# SymphonyLights_SOC_v1_1.net
KiCad netlist of a schematic drawn in Altium Designer
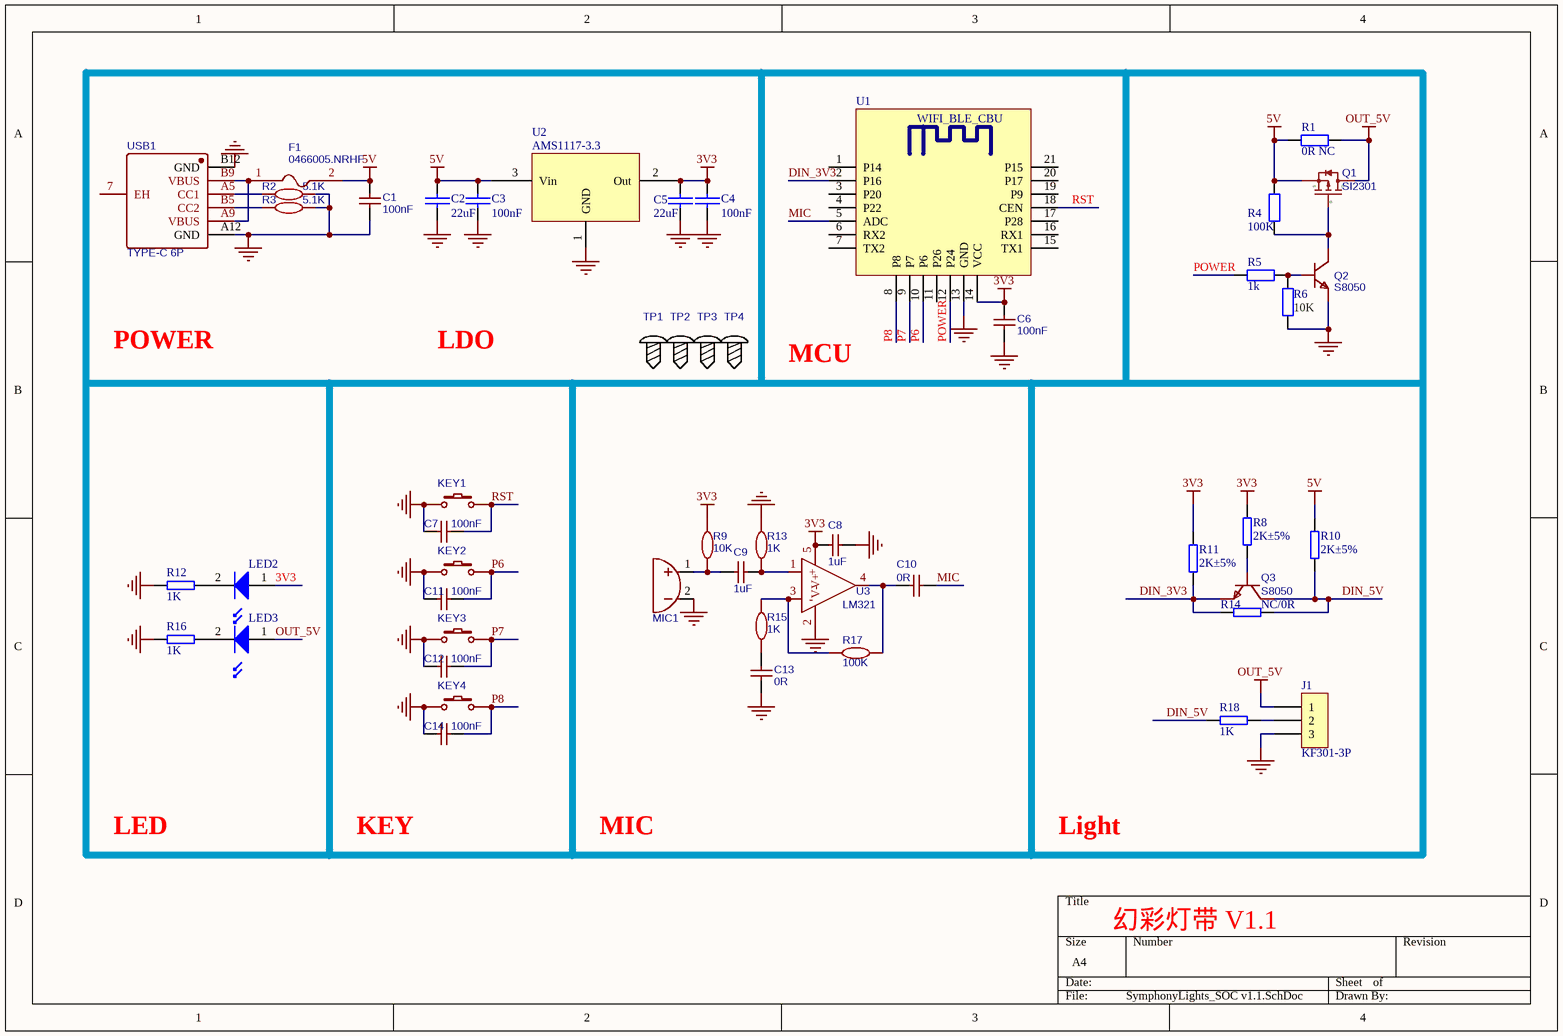
[diagram p0: SymphonyLights_SOC v1.1.SchDoc]

(export (version "E")
  (design (tool "Eeschema 10.0.6"))
  (components
    (comp (ref "C1")
      (value "100nF")
      (footprint "0805C")
      (fields
        (field (name "BOM_MANUFACTURER PART") "0805B104K500NT")
        (field (name "BOM_SUPPLIER PART") "C38141")
      )
      (libsource (lib "altium-import") (part "root_1_100nF_"))
    )
    (comp (ref "C2")
      (value "22uF")
      (footprint "0805C")
      (description "Capacitor")
      (libsource (lib "昊华元件库sch") (part "CAP"))
    )
    (comp (ref "C3")
      (value "100nF")
      (footprint "0805C")
      (description "Capacitor")
      (libsource (lib "昊华元件库sch") (part "CAP"))
    )
    (comp (ref "C4")
      (value "100nF")
      (footprint "0805C")
      (description "Capacitor")
      (libsource (lib "昊华元件库sch") (part "CAP"))
    )
    (comp (ref "C5")
      (value "22uF")
      (footprint "0805C")
      (description "Capacitor")
      (libsource (lib "昊华元件库sch") (part "CAP"))
    )
    (comp (ref "C6")
      (value "100nF")
      (footprint "0805C")
      (fields
        (field (name "BOM_MANUFACTURER PART") "0805B104K500NT")
        (field (name "BOM_SUPPLIER PART") "C38141")
      )
      (libsource (lib "altium-import") (part "root_1_100nF_"))
    )
    (comp (ref "C7")
      (value "100nF")
      (footprint "0805C")
      (fields
        (field (name "BOM_MANUFACTURER PART") "0805B104K500NT")
        (field (name "BOM_SUPPLIER PART") "C38141")
      )
      (libsource (lib "altium-import") (part "root_0_100nF_"))
    )
    (comp (ref "C8")
      (value "1uF")
      (footprint "0805C")
      (fields
        (field (name "BOM_MANUFACTURER PART") "0805B104K500NT")
        (field (name "BOM_SUPPLIER PART") "C38141")
      )
      (libsource (lib "altium-import") (part "root_0_100nF_"))
    )
    (comp (ref "C9")
      (value "1uF")
      (footprint "0805C")
      (fields
        (field (name "BOM_MANUFACTURER PART") "0805B104K500NT")
        (field (name "BOM_SUPPLIER PART") "C38141")
      )
      (libsource (lib "altium-import") (part "root_2_100nF_"))
    )
    (comp (ref "C10")
      (value "0R")
      (footprint "0805C")
      (fields
        (field (name "BOM_MANUFACTURER PART") "0805B104K500NT")
        (field (name "BOM_SUPPLIER PART") "C38141")
      )
      (libsource (lib "altium-import") (part "root_2_100nF_"))
    )
    (comp (ref "C11")
      (value "100nF")
      (footprint "0805C")
      (fields
        (field (name "BOM_MANUFACTURER PART") "0805B104K500NT")
        (field (name "BOM_SUPPLIER PART") "C38141")
      )
      (libsource (lib "altium-import") (part "root_0_100nF_"))
    )
    (comp (ref "C12")
      (value "100nF")
      (footprint "0805C")
      (fields
        (field (name "BOM_MANUFACTURER PART") "0805B104K500NT")
        (field (name "BOM_SUPPLIER PART") "C38141")
      )
      (libsource (lib "altium-import") (part "root_0_100nF_"))
    )
    (comp (ref "C13")
      (value "0R")
      (footprint "0805C")
      (fields
        (field (name "BOM_MANUFACTURER PART") "0805B104K500NT")
        (field (name "BOM_SUPPLIER PART") "C38141")
      )
      (libsource (lib "altium-import") (part "root_3_100nF_"))
    )
    (comp (ref "C14")
      (value "100nF")
      (footprint "0805C")
      (fields
        (field (name "BOM_MANUFACTURER PART") "0805B104K500NT")
        (field (name "BOM_SUPPLIER PART") "C38141")
      )
      (libsource (lib "altium-import") (part "root_0_100nF_"))
    )
    (comp (ref "F1")
      (value "0466005.NRHF")
      (footprint "1206F")
      (fields (field (name "BOM_SUPPLIER PART") "C57525"))
      (libsource (lib "altium-import") (part "root_0_0466005.NRHF_"))
    )
    (comp (ref "J1")
      (value "KF301-3P")
      (footprint "SIP3 - 2.54")
      (description "Connector")
      (libsource (lib "小马元件库sch") (part "CON3"))
    )
    (comp (ref "KEY1")
      (value "RESET")
      (footprint "KEY-SMD_4P-L7.8-W2.8-P4.20-EH")
      (fields
        (field (name "BOM_SUPPLIER PART") "C118141")
        (field (name "BOM_MANUFACTURER PART") "K2-1107ST-A4SW-06")
        (field (name "CONTRIBUTOR") "LCEDA_Lib")
      )
      (libsource (lib "altium-import") (part "root_2_mirrored__"))
    )
    (comp (ref "KEY2")
      (value "场景")
      (footprint "KEY-SMD_4P-L7.8-W2.8-P4.20-EH")
      (fields
        (field (name "BOM_SUPPLIER PART") "C118141")
        (field (name "BOM_MANUFACTURER PART") "K2-1107ST-A4SW-06")
        (field (name "CONTRIBUTOR") "LCEDA_Lib")
      )
      (libsource (lib "altium-import") (part "root_2_mirrored__"))
    )
    (comp (ref "KEY3")
      (value "音乐")
      (footprint "KEY-SMD_4P-L7.8-W2.8-P4.20-EH")
      (fields
        (field (name "BOM_SUPPLIER PART") "C118141")
        (field (name "BOM_MANUFACTURER PART") "K2-1107ST-A4SW-06")
        (field (name "CONTRIBUTOR") "LCEDA_Lib")
      )
      (libsource (lib "altium-import") (part "root_2_mirrored__"))
    )
    (comp (ref "KEY4")
      (value "开关")
      (footprint "KEY-SMD_4P-L7.8-W2.8-P4.20-EH")
      (fields
        (field (name "BOM_SUPPLIER PART") "C118141")
        (field (name "BOM_MANUFACTURER PART") "K2-1107ST-A4SW-06")
        (field (name "CONTRIBUTOR") "LCEDA_Lib")
      )
      (libsource (lib "altium-import") (part "root_2_mirrored__"))
    )
    (comp (ref "LED2")
      (value "LED")
      (footprint "0805LED")
      (fields (field (name "PUBLISHER") "*"))
      (libsource (lib "小马元件库sch") (part "LED"))
    )
    (comp (ref "LED3")
      (value "LED")
      (footprint "0805LED")
      (fields (field (name "PUBLISHER") "*"))
      (libsource (lib "小马元件库sch") (part "LED"))
    )
    (comp (ref "MIC1")
      (value "GMI6050P-66DB")
      (footprint "MIC-TH_BD6.0-P1.90-D0.4-L-RD")
      (fields (field (name "BOM_SUPPLIER PART") "C233954") (field (name "CONTRIBUTOR") "LCSC"))
      (libsource (lib "altium-import") (part "root_3_mirrored_GMI6050P-66DB_"))
    )
    (comp (ref "Q1")
      (value "SI2301")
      (footprint "SOT-23(SOT-23-3)")
      (fields (field (name "BOM_SUPPLIER PART") "C181086") (field (name "CONTRIBUTOR") "lengyuefeng"))
      (libsource (lib "altium-import") (part "root_1_mirrored_SI2301_"))
    )
    (comp (ref "Q2")
      (value "S8050")
      (footprint "SOT-23(SOT-23-3)")
      (fields (field (name "BOM_SUPPLIER PART") "C2146"))
      (libsource (lib "altium-import") (part "root_0_S8050_"))
    )
    (comp (ref "Q3")
      (value "S8050")
      (footprint "SOT-23(SOT-23-3)")
      (fields (field (name "BOM_SUPPLIER PART") "C2146"))
      (libsource (lib "altium-import") (part "root_3_S8050_"))
    )
    (comp (ref "R1")
      (value "0R NC")
      (footprint "0805R")
      (description "Resistor")
      (fields (field (name "PUBLISHER") "Altium Limited"))
      (libsource (lib "") (part "Res2_2"))
    )
    (comp (ref "R2")
      (value "5.1K")
      (footprint "0805R")
      (fields
        (field (name "BOM_SUPPLIER PART") "C328298")
        (field (name "BOM_MANUFACTURER PART") "AECR0402F10K0K9")
        (field (name "CONTRIBUTOR") "LCSC")
      )
      (libsource (lib "altium-import") (part "root_0_10K_"))
    )
    (comp (ref "R3")
      (value "5.1K")
      (footprint "0805R")
      (fields
        (field (name "BOM_SUPPLIER PART") "C328298")
        (field (name "BOM_MANUFACTURER PART") "AECR0402F10K0K9")
        (field (name "CONTRIBUTOR") "LCSC")
      )
      (libsource (lib "altium-import") (part "root_0_10K_"))
    )
    (comp (ref "R4")
      (value "100K")
      (footprint "0805R")
      (description "Resistor")
      (fields (field (name "PUBLISHER") "Altium Limited"))
      (libsource (lib "") (part "Res2_1"))
    )
    (comp (ref "R5")
      (value "1k")
      (footprint "0805R")
      (description "Resistor")
      (fields (field (name "PUBLISHER") "Altium Limited"))
      (libsource (lib "") (part "Res2_2"))
    )
    (comp (ref "R6")
      (value "10K")
      (footprint "0805R")
      (description "Resistor")
      (fields (field (name "PUBLISHER") "Altium Limited"))
      (libsource (lib "*") (part "Res2"))
    )
    (comp (ref "R8") (value "2K±5%") (footprint "0805R") (libsource (lib "昊华元件库sch") (part "RES5")))
    (comp (ref "R9")
      (value "10K")
      (footprint "0805R")
      (fields
        (field (name "BOM_SUPPLIER PART") "C328298")
        (field (name "BOM_MANUFACTURER PART") "AECR0402F10K0K9")
        (field (name "CONTRIBUTOR") "LCSC")
      )
      (libsource (lib "altium-import") (part "root_3_10K_"))
    )
    (comp (ref "R10") (value "2K±5%") (footprint "0805R") (libsource (lib "昊华元件库sch") (part "RES5")))
    (comp (ref "R11") (value "2K±5%") (footprint "0805R") (libsource (lib "昊华元件库sch") (part "RES5")))
    (comp (ref "R12") (value "1K") (footprint "0805R") (libsource (lib "昊华元件库sch") (part "RES5")))
    (comp (ref "R13")
      (value "1K")
      (footprint "0805R")
      (fields
        (field (name "BOM_SUPPLIER PART") "C328298")
        (field (name "BOM_MANUFACTURER PART") "AECR0402F10K0K9")
        (field (name "CONTRIBUTOR") "LCSC")
      )
      (libsource (lib "altium-import") (part "root_3_10K_"))
    )
    (comp (ref "R14") (value "NC/0R") (footprint "0805R") (libsource (lib "昊华元件库sch") (part "RES5")))
    (comp (ref "R15")
      (value "1K")
      (footprint "0805R")
      (fields
        (field (name "BOM_SUPPLIER PART") "C328298")
        (field (name "BOM_MANUFACTURER PART") "AECR0402F10K0K9")
        (field (name "CONTRIBUTOR") "LCSC")
      )
      (libsource (lib "altium-import") (part "root_1_10K_"))
    )
    (comp (ref "R16") (value "1K") (footprint "0805R") (libsource (lib "昊华元件库sch") (part "RES5")))
    (comp (ref "R17")
      (value "100K")
      (footprint "0805R")
      (fields
        (field (name "BOM_SUPPLIER PART") "C328298")
        (field (name "BOM_MANUFACTURER PART") "AECR0402F10K0K9")
        (field (name "CONTRIBUTOR") "LCSC")
      )
      (libsource (lib "altium-import") (part "root_0_10K_"))
    )
    (comp (ref "R18") (value "1K") (footprint "0805R") (libsource (lib "昊华元件库sch") (part "RES5")))
    (comp (ref "TP1")
      (value "~")
      (footprint "M3螺丝孔")
      (fields (field (name "CONTRIBUTOR") "455553Z"))
      (libsource (lib "altium-import") (part "root_0__"))
    )
    (comp (ref "TP2")
      (value "~")
      (footprint "M3螺丝孔")
      (fields (field (name "CONTRIBUTOR") "455553Z"))
      (libsource (lib "altium-import") (part "root_0__"))
    )
    (comp (ref "TP3")
      (value "~")
      (footprint "M3螺丝孔")
      (fields (field (name "CONTRIBUTOR") "455553Z"))
      (libsource (lib "altium-import") (part "root_0__"))
    )
    (comp (ref "TP4")
      (value "~")
      (footprint "M3螺丝孔")
      (fields (field (name "CONTRIBUTOR") "455553Z"))
      (libsource (lib "altium-import") (part "root_0__"))
    )
    (comp (ref "U1")
      (value "WIFI_BLE_CBU")
      (footprint "WIFI_BLE_CBU")
      (description "Module")
      (libsource (lib "TYModeSchlib V03") (part "WIFI_BLE_CBU"))
    )
    (comp (ref "U2") (value "AMS1117-3.3") (footprint "SOT-223") (libsource (lib "mylib") (part "GM1117")))
    (comp (ref "U3")
      (value "LM321")
      (footprint "SOT-23-5")
      (fields (field (name "CONTRIBUTOR") "KiCAD"))
      (libsource (lib "altium-import") (part "root_0_LM321_"))
    )
    (comp (ref "USB1")
      (value "TYPE-C 6P")
      (footprint "TYPE-C-SMD_TYPE-C-6P")
      (fields
        (field (name "BOM_SUPPLIER PART") "C668623")
        (field (name "BOM_MANUFACTURER PART") "TYPE-C 6P(073)")
        (field (name "CONTRIBUTOR") "LCSC")
      )
      (libsource (lib "altium-import") (part "root_0_mirrored_TYPE-C 6P(073)_"))
    )
  )
  (nets
    (net (code "1") (name "/DIN_3V3") (class "Default")
      (node (ref "Q3") (pin "2") (pinfunction "E_2") (pintype "passive"))
      (node (ref "R11") (pin "2") (pinfunction "2_2") (pintype "passive"))
      (node (ref "R14") (pin "1") (pinfunction "1_1") (pintype "passive"))
      (node (ref "U1") (pin "2") (pinfunction "P16_2") (pintype "passive"))
    )
    (net (code "2") (name "/DIN_5V") (class "Default")
      (node (ref "Q3") (pin "3") (pinfunction "C_3") (pintype "passive"))
      (node (ref "R10") (pin "2") (pinfunction "2_2") (pintype "passive"))
      (node (ref "R14") (pin "2") (pinfunction "2_2") (pintype "passive"))
      (node (ref "R18") (pin "1") (pinfunction "1_1") (pintype "passive"))
    )
    (net (code "3") (name "/MIC") (class "Default")
      (node (ref "C10") (pin "1") (pinfunction "1_1") (pintype "passive"))
      (node (ref "U1") (pin "5") (pinfunction "ADC_5") (pintype "passive"))
    )
    (net (code "4") (name "/P6") (class "Default")
      (node (ref "C11") (pin "2") (pinfunction "2_2") (pintype "passive"))
      (node (ref "KEY2") (pin "1") (pinfunction "1_1") (pintype "passive"))
      (node (ref "U1") (pin "10") (pinfunction "P6_10") (pintype "passive"))
    )
    (net (code "5") (name "/P7") (class "Default")
      (node (ref "C12") (pin "2") (pinfunction "2_2") (pintype "passive"))
      (node (ref "KEY3") (pin "1") (pinfunction "1_1") (pintype "passive"))
      (node (ref "U1") (pin "9") (pinfunction "P7_9") (pintype "passive"))
    )
    (net (code "6") (name "/P8") (class "Default")
      (node (ref "C14") (pin "2") (pinfunction "2_2") (pintype "passive"))
      (node (ref "KEY4") (pin "1") (pinfunction "1_1") (pintype "passive"))
      (node (ref "U1") (pin "8") (pinfunction "P8_8") (pintype "passive"))
    )
    (net (code "7") (name "/POWER") (class "Default")
      (node (ref "R5") (pin "1") (pinfunction "1_1") (pintype "passive"))
      (node (ref "U1") (pin "12") (pinfunction "P24_12") (pintype "passive"))
    )
    (net (code "8") (name "/RST") (class "Default")
      (node (ref "C7") (pin "2") (pinfunction "2_2") (pintype "passive"))
      (node (ref "KEY1") (pin "1") (pinfunction "1_1") (pintype "passive"))
      (node (ref "U1") (pin "18") (pinfunction "CEN_18") (pintype "passive"))
    )
    (net (code "9") (name "3V3") (class "Default")
      (node (ref "C4") (pin "1") (pinfunction "1_1") (pintype "passive"))
      (node (ref "C5") (pin "1") (pinfunction "1_1") (pintype "passive"))
      (node (ref "C6") (pin "2") (pinfunction "2_2") (pintype "passive"))
      (node (ref "C8") (pin "1") (pinfunction "1_1") (pintype "passive"))
      (node (ref "LED2") (pin "1") (pinfunction "1_1") (pintype "passive"))
      (node (ref "R11") (pin "1") (pinfunction "1_1") (pintype "passive"))
      (node (ref "R8") (pin "1") (pinfunction "1_1") (pintype "passive"))
      (node (ref "R9") (pin "1") (pinfunction "1_1") (pintype "passive"))
      (node (ref "U1") (pin "14") (pinfunction "VCC_14") (pintype "passive"))
      (node (ref "U2") (pin "2") (pinfunction "Out_2") (pintype "passive"))
      (node (ref "U3") (pin "5") (pinfunction "V+_5") (pintype "passive"))
    )
    (net (code "10") (name "5V") (class "Default")
      (node (ref "C1") (pin "2") (pinfunction "2_2") (pintype "passive"))
      (node (ref "C2") (pin "1") (pinfunction "1_1") (pintype "passive"))
      (node (ref "C3") (pin "1") (pinfunction "1_1") (pintype "passive"))
      (node (ref "F1") (pin "2") (pinfunction "2_2") (pintype "passive"))
      (node (ref "Q1") (pin "2") (pinfunction "S_2") (pintype "passive"))
      (node (ref "R1") (pin "1") (pinfunction "1_1") (pintype "passive"))
      (node (ref "R10") (pin "1") (pinfunction "1_1") (pintype "passive"))
      (node (ref "R4") (pin "2") (pinfunction "2_2") (pintype "passive"))
      (node (ref "U2") (pin "3") (pinfunction "Vin_3") (pintype "passive"))
    )
    (net (code "11") (name "GND") (class "Default")
      (node (ref "C1") (pin "1") (pinfunction "1_1") (pintype "passive"))
      (node (ref "C11") (pin "1") (pinfunction "1_1") (pintype "passive"))
      (node (ref "C12") (pin "1") (pinfunction "1_1") (pintype "passive"))
      (node (ref "C13") (pin "2") (pinfunction "2_2") (pintype "passive"))
      (node (ref "C14") (pin "1") (pinfunction "1_1") (pintype "passive"))
      (node (ref "C2") (pin "2") (pinfunction "2_2") (pintype "passive"))
      (node (ref "C3") (pin "2") (pinfunction "2_2") (pintype "passive"))
      (node (ref "C4") (pin "2") (pinfunction "2_2") (pintype "passive"))
      (node (ref "C5") (pin "2") (pinfunction "2_2") (pintype "passive"))
      (node (ref "C6") (pin "1") (pinfunction "1_1") (pintype "passive"))
      (node (ref "C7") (pin "1") (pinfunction "1_1") (pintype "passive"))
      (node (ref "C8") (pin "2") (pinfunction "2_2") (pintype "passive"))
      (node (ref "J1") (pin "3") (pinfunction "3_3") (pintype "passive"))
      (node (ref "KEY1") (pin "2") (pinfunction "2_2") (pintype "passive"))
      (node (ref "KEY2") (pin "2") (pinfunction "2_2") (pintype "passive"))
      (node (ref "KEY3") (pin "2") (pinfunction "2_2") (pintype "passive"))
      (node (ref "KEY4") (pin "2") (pinfunction "2_2") (pintype "passive"))
      (node (ref "MIC1") (pin "2") (pinfunction "2_2") (pintype "passive"))
      (node (ref "Q2") (pin "2") (pinfunction "E_2") (pintype "passive"))
      (node (ref "R12") (pin "2") (pinfunction "2_2") (pintype "passive"))
      (node (ref "R13") (pin "1") (pinfunction "1_1") (pintype "passive"))
      (node (ref "R16") (pin "2") (pinfunction "2_2") (pintype "passive"))
      (node (ref "R2") (pin "2") (pinfunction "2_2") (pintype "passive"))
      (node (ref "R3") (pin "2") (pinfunction "2_2") (pintype "passive"))
      (node (ref "R6") (pin "2") (pinfunction "2_2") (pintype "passive"))
      (node (ref "U1") (pin "13") (pinfunction "GND_13") (pintype "passive"))
      (node (ref "U2") (pin "1") (pinfunction "GND_1") (pintype "passive"))
      (node (ref "U3") (pin "2") (pinfunction "V-_2") (pintype "passive"))
      (node (ref "USB1") (pin "A12") (pinfunction "GND_A12") (pintype "passive"))
      (node (ref "USB1") (pin "B12") (pinfunction "GND_B12") (pintype "passive"))
    )
    (net (code "12") (name "Net-(C9-Pad2)") (class "Default")
      (node (ref "C9") (pin "2") (pinfunction "2_2") (pintype "passive"))
      (node (ref "MIC1") (pin "1") (pinfunction "1_1") (pintype "passive"))
      (node (ref "R9") (pin "2") (pinfunction "2_2") (pintype "passive"))
    )
    (net (code "13") (name "Net-(C10-Pad2)") (class "Default")
      (node (ref "C10") (pin "2") (pinfunction "2_2") (pintype "passive"))
      (node (ref "R17") (pin "2") (pinfunction "2_2") (pintype "passive"))
      (node (ref "U3") (pin "4") (pintype "passive"))
    )
    (net (code "14") (name "Net-(C13-Pad1)") (class "Default")
      (node (ref "C13") (pin "1") (pinfunction "1_1") (pintype "passive"))
      (node (ref "R15") (pin "1") (pinfunction "1_1") (pintype "passive"))
    )
    (net (code "15") (name "Net-(F1-Pad1)") (class "Default")
      (node (ref "F1") (pin "1") (pinfunction "1_1") (pintype "passive"))
      (node (ref "USB1") (pin "A9") (pinfunction "VBUS_A9") (pintype "passive"))
      (node (ref "USB1") (pin "B9") (pinfunction "VBUS_B9") (pintype "passive"))
    )
    (net (code "16") (name "Net-(J1-Pad2)") (class "Default")
      (node (ref "J1") (pin "2") (pinfunction "2_2") (pintype "passive"))
      (node (ref "R18") (pin "2") (pinfunction "2_2") (pintype "passive"))
    )
    (net (code "17") (name "Net-(LED2-Pad2)") (class "Default")
      (node (ref "LED2") (pin "2") (pinfunction "2_2") (pintype "passive"))
      (node (ref "R12") (pin "1") (pinfunction "1_1") (pintype "passive"))
    )
    (net (code "18") (name "Net-(LED3-Pad2)") (class "Default")
      (node (ref "LED3") (pin "2") (pinfunction "2_2") (pintype "passive"))
      (node (ref "R16") (pin "1") (pinfunction "1_1") (pintype "passive"))
    )
    (net (code "19") (name "Net-(Q1-G)") (class "Default")
      (node (ref "Q1") (pin "1") (pinfunction "G_1") (pintype "passive"))
      (node (ref "Q2") (pin "3") (pinfunction "C_3") (pintype "passive"))
      (node (ref "R4") (pin "1") (pinfunction "1_1") (pintype "passive"))
    )
    (net (code "20") (name "Net-(Q2-B)") (class "Default")
      (node (ref "Q2") (pin "1") (pinfunction "B_1") (pintype "passive"))
      (node (ref "R5") (pin "2") (pinfunction "2_2") (pintype "passive"))
      (node (ref "R6") (pin "1") (pinfunction "1_1") (pintype "passive"))
    )
    (net (code "21") (name "Net-(Q3-B)") (class "Default")
      (node (ref "Q3") (pin "1") (pinfunction "B_1") (pintype "passive"))
      (node (ref "R8") (pin "2") (pinfunction "2_2") (pintype "passive"))
    )
    (net (code "22") (name "Net-(U3-+)") (class "Default")
      (node (ref "C9") (pin "1") (pinfunction "1_1") (pintype "passive"))
      (node (ref "R13") (pin "2") (pinfunction "2_2") (pintype "passive"))
      (node (ref "U3") (pin "1") (pinfunction "+_1") (pintype "passive"))
    )
    (net (code "23") (name "Net-(U3--)") (class "Default")
      (node (ref "R15") (pin "2") (pinfunction "2_2") (pintype "passive"))
      (node (ref "R17") (pin "1") (pinfunction "1_1") (pintype "passive"))
      (node (ref "U3") (pin "3") (pinfunction "-_3") (pintype "passive"))
    )
    (net (code "24") (name "Net-(USB1-CC1)") (class "Default")
      (node (ref "R2") (pin "1") (pinfunction "1_1") (pintype "passive"))
      (node (ref "USB1") (pin "A5") (pinfunction "CC1_A5") (pintype "passive"))
    )
    (net (code "25") (name "Net-(USB1-CC2)") (class "Default")
      (node (ref "R3") (pin "1") (pinfunction "1_1") (pintype "passive"))
      (node (ref "USB1") (pin "B5") (pinfunction "CC2_B5") (pintype "passive"))
    )
    (net (code "26") (name "OUT_5V") (class "Default")
      (node (ref "J1") (pin "1") (pinfunction "1_1") (pintype "passive"))
      (node (ref "LED3") (pin "1") (pinfunction "1_1") (pintype "passive"))
      (node (ref "Q1") (pin "3") (pinfunction "D_3") (pintype "passive"))
      (node (ref "R1") (pin "2") (pinfunction "2_2") (pintype "passive"))
    )
    (net (code "27") (name "unconnected-(U1-P9-Pad19)") (class "Default")
      (node (ref "U1") (pin "19") (pinfunction "P9_19") (pintype "passive"))
    )
    (net (code "28") (name "unconnected-(U1-P14-Pad1)") (class "Default")
      (node (ref "U1") (pin "1") (pinfunction "P14_1") (pintype "passive"))
    )
    (net (code "29") (name "unconnected-(U1-P15-Pad21)") (class "Default")
      (node (ref "U1") (pin "21") (pinfunction "P15_21") (pintype "passive"))
    )
    (net (code "30") (name "unconnected-(U1-P17-Pad20)") (class "Default")
      (node (ref "U1") (pin "20") (pinfunction "P17_20") (pintype "passive"))
    )
    (net (code "31") (name "unconnected-(U1-P20-Pad3)") (class "Default")
      (node (ref "U1") (pin "3") (pinfunction "P20_3") (pintype "passive"))
    )
    (net (code "32") (name "unconnected-(U1-P22-Pad4)") (class "Default")
      (node (ref "U1") (pin "4") (pinfunction "P22_4") (pintype "passive"))
    )
    (net (code "33") (name "unconnected-(U1-P26-Pad11)") (class "Default")
      (node (ref "U1") (pin "11") (pinfunction "P26_11") (pintype "passive"))
    )
    (net (code "34") (name "unconnected-(U1-P28-Pad17)") (class "Default")
      (node (ref "U1") (pin "17") (pinfunction "P28_17") (pintype "passive"))
    )
    (net (code "35") (name "unconnected-(U1-RX1-Pad16)") (class "Default")
      (node (ref "U1") (pin "16") (pinfunction "RX1_16") (pintype "passive"))
    )
    (net (code "36") (name "unconnected-(U1-RX2-Pad6)") (class "Default")
      (node (ref "U1") (pin "6") (pinfunction "RX2_6") (pintype "passive"))
    )
    (net (code "37") (name "unconnected-(U1-TX1-Pad15)") (class "Default")
      (node (ref "U1") (pin "15") (pinfunction "TX1_15") (pintype "passive"))
    )
    (net (code "38") (name "unconnected-(U1-TX2-Pad7)") (class "Default")
      (node (ref "U1") (pin "7") (pinfunction "TX2_7") (pintype "passive"))
    )
    (net (code "39") (name "unconnected-(USB1-EH-Pad7)") (class "Default")
      (node (ref "USB1") (pin "7") (pinfunction "EH_7") (pintype "passive"))
    )
  )
)
